# RKJXT1_Board_v6.net
KiCad netlist of a schematic drawn in EAGLE
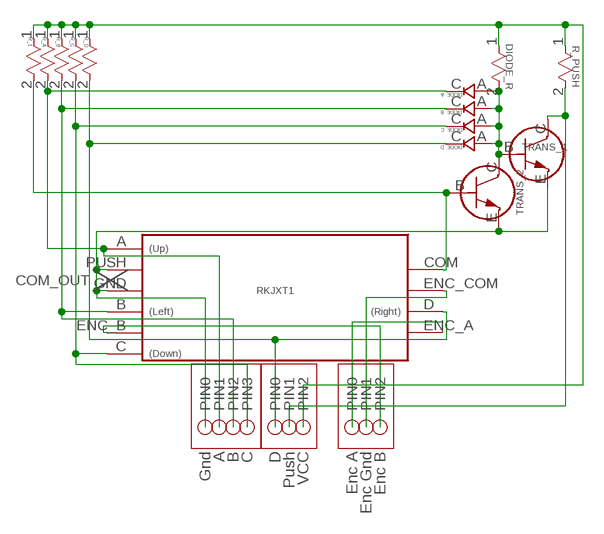
[diagram p0: schematic, sheet 1]

(export (version "E")
  (design (tool "Eeschema 10.0.6"))
  (components
    (comp (ref "DIODE_A")
      (value "DIODE_SCHOTTKY_SMD_USC_TOS")
      (footprint "eagle-import:DIODE_SCHOTTKY_SMD_USC_TOS")
      (libsource (lib "eagle-import") (part "DIODE_SCHOTTKY_SMD_USC_TOS"))
    )
    (comp (ref "DIODE_B")
      (value "DIODE_SCHOTTKY_SMD_USC_TOS")
      (footprint "eagle-import:DIODE_SCHOTTKY_SMD_USC_TOS")
      (libsource (lib "eagle-import") (part "DIODE_SCHOTTKY_SMD_USC_TOS"))
    )
    (comp (ref "DIODE_C")
      (value "DIODE_SCHOTTKY_SMD_USC_TOS")
      (footprint "eagle-import:DIODE_SCHOTTKY_SMD_USC_TOS")
      (libsource (lib "eagle-import") (part "DIODE_SCHOTTKY_SMD_USC_TOS"))
    )
    (comp (ref "DIODE_D")
      (value "DIODE_SCHOTTKY_SMD_USC_TOS")
      (footprint "eagle-import:DIODE_SCHOTTKY_SMD_USC_TOS")
      (libsource (lib "eagle-import") (part "DIODE_SCHOTTKY_SMD_USC_TOS"))
    )
    (comp (ref "DIODE_R")
      (value "RESISTOR_1K_SMD_RNCP0805FTD1K00STA_RNCP0805_STP-L")
      (footprint "eagle-import:STA_RNCP0805_STP-L")
      (fields (field (name "MANUFACTURER_PART_NUMBER") "RNCP0805FTD1K00"))
      (libsource (lib "eagle-import") (part "RESISTOR_1K_SMD_RNCP0805FTD1K00STA_RNCP0805_STP-L"))
    )
    (comp (ref "RKJXT1")
      (value "RKJXT1_V3")
      (footprint "eagle-import:RKJXT1_V3")
      (libsource (lib "eagle-import") (part "RKJXT1_V3"))
    )
    (comp (ref "R_1")
      (value "RESISTOR_1K_SMD_RNCP0805FTD1K00STA_RNCP0805_STP-L")
      (footprint "eagle-import:STA_RNCP0805_STP-L")
      (fields (field (name "MANUFACTURER_PART_NUMBER") "RNCP0805FTD1K00"))
      (libsource (lib "eagle-import") (part "RESISTOR_1K_SMD_RNCP0805FTD1K00STA_RNCP0805_STP-L"))
    )
    (comp (ref "R_A")
      (value "RESISTOR_1K_SMD_RNCP0805FTD1K00STA_RNCP0805_STP-L")
      (footprint "eagle-import:STA_RNCP0805_STP-L")
      (fields (field (name "MANUFACTURER_PART_NUMBER") "RNCP0805FTD1K00"))
      (libsource (lib "eagle-import") (part "RESISTOR_1K_SMD_RNCP0805FTD1K00STA_RNCP0805_STP-L"))
    )
    (comp (ref "R_B")
      (value "RESISTOR_1K_SMD_RNCP0805FTD1K00STA_RNCP0805_STP-L")
      (footprint "eagle-import:STA_RNCP0805_STP-L")
      (fields (field (name "MANUFACTURER_PART_NUMBER") "RNCP0805FTD1K00"))
      (libsource (lib "eagle-import") (part "RESISTOR_1K_SMD_RNCP0805FTD1K00STA_RNCP0805_STP-L"))
    )
    (comp (ref "R_C")
      (value "RESISTOR_1K_SMD_RNCP0805FTD1K00STA_RNCP0805_STP-L")
      (footprint "eagle-import:STA_RNCP0805_STP-L")
      (fields (field (name "MANUFACTURER_PART_NUMBER") "RNCP0805FTD1K00"))
      (libsource (lib "eagle-import") (part "RESISTOR_1K_SMD_RNCP0805FTD1K00STA_RNCP0805_STP-L"))
    )
    (comp (ref "R_D")
      (value "RESISTOR_1K_SMD_RNCP0805FTD1K00STA_RNCP0805_STP-L")
      (footprint "eagle-import:STA_RNCP0805_STP-L")
      (fields (field (name "MANUFACTURER_PART_NUMBER") "RNCP0805FTD1K00"))
      (libsource (lib "eagle-import") (part "RESISTOR_1K_SMD_RNCP0805FTD1K00STA_RNCP0805_STP-L"))
    )
    (comp (ref "R_PUSH")
      (value "RESISTOR_1K_SMD_RNCP0805FTD1K00STA_RNCP0805_STP-L")
      (footprint "eagle-import:STA_RNCP0805_STP-L")
      (fields (field (name "MANUFACTURER_PART_NUMBER") "RNCP0805FTD1K00"))
      (libsource (lib "eagle-import") (part "RESISTOR_1K_SMD_RNCP0805FTD1K00STA_RNCP0805_STP-L"))
    )
    (comp (ref "TRANS_1")
      (value "TRANS_NPN_SMD_MMBT3904-TPSOT-23_MCC-L")
      (footprint "eagle-import:SOT-23_MCC-L")
      (fields
        (field (name "MANUFACTURER_PART_NUMBER") "MMBT3904-TP")
        (field (name "COPYRIGHT") "Copyright (C) 2018 Accelerated Designs. All rights reserved")
      )
      (libsource (lib "eagle-import") (part "TRANS_NPN_SMD_MMBT3904-TPSOT-23_MCC-L"))
    )
    (comp (ref "TRANS_2")
      (value "TRANS_NPN_SMD_MMBT3904-TPSOT-23_MCC-L")
      (footprint "eagle-import:SOT-23_MCC-L")
      (fields
        (field (name "MANUFACTURER_PART_NUMBER") "MMBT3904-TP")
        (field (name "COPYRIGHT") "Copyright (C) 2018 Accelerated Designs. All rights reserved")
      )
      (libsource (lib "eagle-import") (part "TRANS_NPN_SMD_MMBT3904-TPSOT-23_MCC-L"))
    )
    (comp (ref "U$4")
      (value "JST_ZH_3PIN_NO_GND")
      (footprint "eagle-import:JST_ZH_3PIN_NO_GND")
      (fields
        (field (name "LABEL") "Enc Pins")
        (field (name "PIN0") "EncA")
        (field (name "PIN1") "Com")
        (field (name "PIN2") "EncB")
      )
      (libsource (lib "eagle-import") (part "JST_ZH_3PIN_NO_GND"))
    )
    (comp (ref "U$5")
      (value "JST_ZH_3PIN_NO_GND")
      (footprint "eagle-import:JST_ZH_3PIN_NO_GND")
      (fields (field (name "PIN0") "D") (field (name "PIN1") "Push") (field (name "PIN2") "Vcc"))
      (libsource (lib "eagle-import") (part "JST_ZH_3PIN_NO_GND"))
    )
    (comp (ref "U$6")
      (value "JST_ZH_4PIN")
      (footprint "eagle-import:JST_ZH_4PIN")
      (fields
        (field (name "LABEL") "Hat Pins")
        (field (name "PIN0") "Gnd")
        (field (name "PIN1") "A")
        (field (name "PIN2") "B")
        (field (name "PIN3") "C")
      )
      (libsource (lib "eagle-import") (part "JST_ZH_4PIN"))
    )
  )
  (nets
    (net (code "1") (name "Net-(DIODE_A-PadA)") (class "Default")
      (node (ref "DIODE_A") (pin "A") (pinfunction "A_A") (pintype "passive"))
      (node (ref "DIODE_B") (pin "A") (pinfunction "A_A") (pintype "passive"))
      (node (ref "DIODE_C") (pin "A") (pinfunction "A_A") (pintype "passive"))
      (node (ref "DIODE_D") (pin "A") (pinfunction "A_A") (pintype "passive"))
      (node (ref "DIODE_R") (pin "2") (pinfunction "2_2") (pintype "passive"))
      (node (ref "TRANS_1") (pin "B") (pinfunction "B_B") (pintype "passive"))
      (node (ref "TRANS_2") (pin "C") (pinfunction "C_C") (pintype "passive"))
    )
    (net (code "2") (name "Net-(DIODE_A-PadC)") (class "Default")
      (node (ref "DIODE_A") (pin "C") (pinfunction "C_C") (pintype "passive"))
      (node (ref "RKJXT1") (pin "A") (pinfunction "A_A") (pintype "bidirectional"))
      (node (ref "R_A") (pin "2") (pinfunction "2_2") (pintype "passive"))
      (node (ref "U$6") (pin "PIN1") (pinfunction "PIN1_PIN1") (pintype "bidirectional"))
    )
    (net (code "3") (name "Net-(DIODE_B-PadC)") (class "Default")
      (node (ref "DIODE_B") (pin "C") (pinfunction "C_C") (pintype "passive"))
      (node (ref "RKJXT1") (pin "B") (pinfunction "B_B") (pintype "bidirectional"))
      (node (ref "R_B") (pin "2") (pinfunction "2_2") (pintype "passive"))
      (node (ref "U$6") (pin "PIN2") (pinfunction "PIN2_PIN2") (pintype "bidirectional"))
    )
    (net (code "4") (name "Net-(DIODE_C-PadC)") (class "Default")
      (node (ref "DIODE_C") (pin "C") (pinfunction "C_C") (pintype "passive"))
      (node (ref "RKJXT1") (pin "C") (pinfunction "C_C") (pintype "bidirectional"))
      (node (ref "R_C") (pin "2") (pinfunction "2_2") (pintype "passive"))
      (node (ref "U$6") (pin "PIN3") (pinfunction "PIN3_PIN3") (pintype "bidirectional"))
    )
    (net (code "5") (name "Net-(DIODE_D-PadC)") (class "Default")
      (node (ref "DIODE_D") (pin "C") (pinfunction "C_C") (pintype "passive"))
      (node (ref "RKJXT1") (pin "D") (pinfunction "D_D") (pintype "bidirectional"))
      (node (ref "R_D") (pin "2") (pinfunction "2_2") (pintype "passive"))
      (node (ref "U$5") (pin "PIN0") (pinfunction "PIN0_PIN0") (pintype "bidirectional"))
    )
    (net (code "6") (name "Net-(DIODE_R-Pad1)") (class "Default")
      (node (ref "DIODE_R") (pin "1") (pinfunction "1_1") (pintype "passive"))
      (node (ref "R_1") (pin "1") (pinfunction "1_1") (pintype "passive"))
      (node (ref "R_A") (pin "1") (pinfunction "1_1") (pintype "passive"))
      (node (ref "R_B") (pin "1") (pinfunction "1_1") (pintype "passive"))
      (node (ref "R_C") (pin "1") (pinfunction "1_1") (pintype "passive"))
      (node (ref "R_D") (pin "1") (pinfunction "1_1") (pintype "passive"))
      (node (ref "R_PUSH") (pin "1") (pinfunction "1_1") (pintype "passive"))
      (node (ref "U$5") (pin "PIN2") (pinfunction "PIN2_PIN2") (pintype "bidirectional"))
    )
    (net (code "7") (name "Net-(RKJXT1-PadCOM)") (class "Default")
      (node (ref "RKJXT1") (pin "COM") (pinfunction "COM_COM") (pintype "bidirectional"))
      (node (ref "R_1") (pin "2") (pinfunction "2_2") (pintype "passive"))
      (node (ref "TRANS_2") (pin "B") (pinfunction "B_B") (pintype "passive"))
    )
    (net (code "8") (name "Net-(RKJXT1-PadENC_A)") (class "Default")
      (node (ref "RKJXT1") (pin "ENC_A") (pinfunction "ENC_A_ENC_A") (pintype "bidirectional"))
      (node (ref "U$4") (pin "PIN0") (pinfunction "PIN0_PIN0") (pintype "bidirectional"))
    )
    (net (code "9") (name "Net-(RKJXT1-PadENC_B)") (class "Default")
      (node (ref "RKJXT1") (pin "ENC_B") (pinfunction "ENC_B_ENC_B") (pintype "bidirectional"))
      (node (ref "U$4") (pin "PIN2") (pinfunction "PIN2_PIN2") (pintype "bidirectional"))
    )
    (net (code "10") (name "Net-(RKJXT1-PadENC_COM)") (class "Default")
      (node (ref "RKJXT1") (pin "ENC_COM") (pinfunction "ENC_COM_ENC_COM") (pintype "bidirectional"))
      (node (ref "U$4") (pin "PIN1") (pinfunction "PIN1_PIN1") (pintype "bidirectional"))
    )
    (net (code "11") (name "Net-(RKJXT1-PadGND)") (class "Default")
      (node (ref "RKJXT1") (pin "GND") (pinfunction "GND_GND") (pintype "bidirectional"))
      (node (ref "RKJXT1") (pin "PUSH") (pinfunction "PUSH_PUSH") (pintype "bidirectional"))
      (node (ref "TRANS_1") (pin "E") (pinfunction "E_E") (pintype "passive"))
      (node (ref "TRANS_2") (pin "E") (pinfunction "E_E") (pintype "passive"))
      (node (ref "U$6") (pin "PIN0") (pinfunction "PIN0_PIN0") (pintype "bidirectional"))
    )
    (net (code "12") (name "Net-(R_PUSH-Pad2)") (class "Default")
      (node (ref "R_PUSH") (pin "2") (pinfunction "2_2") (pintype "passive"))
      (node (ref "TRANS_1") (pin "C") (pinfunction "C_C") (pintype "passive"))
      (node (ref "U$5") (pin "PIN1") (pinfunction "PIN1_PIN1") (pintype "bidirectional"))
    )
  )
)
